# Channel.net
KiCad netlist of a schematic drawn in Altium Designer
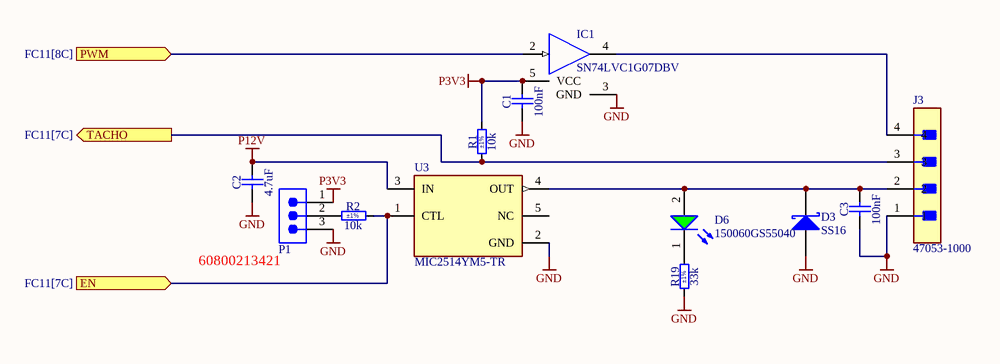
[diagram p0: Channel.SchDoc]

(export (version "E")
  (design (tool "Eeschema 10.0.6"))
  (components
    (comp (ref "C1")
      (value "100nF")
      (footprint "CAPC1005X55N")
      (description "Non-polarised capacitor")
      (fields
        (field (name "PART NUMBER") "CC0402_100NF_16V_10%_X5R")
        (field (name "VOLTAGE") "16V")
        (field (name "AUTHOR") "CERN DEM JLC")
      )
      (libsource (lib "Capacitors") (part "Capacitor - non polarized"))
    )
    (comp (ref "C2")
      (value "4.7uF")
      (footprint "CAPC1709X95N")
      (description "Non-polarised capacitor")
      (fields
        (field (name "PART NUMBER") "CC0603_4.7UF_16V_10%_X5R")
        (field (name "VOLTAGE") "16V")
        (field (name "AUTHOR") "CERN DEM JLC")
      )
      (libsource (lib "Capacitors") (part "Capacitor - non polarized"))
    )
    (comp (ref "C3")
      (value "100nF")
      (footprint "CAPC1005X55N")
      (description "Non-polarised capacitor")
      (fields
        (field (name "PART NUMBER") "CC0402_100NF_16V_10%_X5R")
        (field (name "VOLTAGE") "16V")
        (field (name "AUTHOR") "CERN DEM JLC")
      )
      (libsource (lib "Capacitors") (part "Capacitor - non polarized"))
    )
    (comp (ref "D3")
      (value "SS16")
      (footprint "FAIR-SMA-2_B_V")
      (description "Schottky Rectifier, 700 mV, -65 to 125 degC, 2-Pin SMA, RoHS, Tape and Reel")
      (fields (field (name "MANUFACTURER") "FairchildSemiconductor"))
      (libsource (lib "Altium Content Vault") (part "DSKY-AK-2"))
    )
    (comp (ref "D6")
      (value "150060GS55040")
      (footprint "WL-SMCD_0603")
      (description "150060GS55040 WL-SMCD SMT Mono-color Chip LED Diffused")
      (libsource (lib "Altium Content Vault") (part "LED_Green_2A-1K"))
    )
    (comp (ref "IC1")
      (value "SN74LVC1G07DBV")
      (footprint "SOT95P280X145-5N")
      (description "Single Buffer/Driver With Open-Drain Output")
      (fields (field (name "MANUFACTURER") "TEXAS INSTRUMENTS") (field (name "AUTHOR") "CERN DEM BC"))
      (libsource (lib "ICs And Semiconductors") (part "741G07"))
    )
    (comp (ref "J3")
      (value "47053-1000")
      (footprint "FP-470531000-MFG")
      (description "CONN HEADER VERT 4POS 2.54MM")
      (libsource (lib "Altium Content Vault") (part "299a8cea1bdcbc3624fe62c390fa72c"))
    )
    (comp (ref "P1")
      (value "~")
      (footprint "62000311121")
      (description "WR-PHD Pin Header, THT, Vertical, pitch 2mm, 1 Row, 3P")
      (fields
        (field (name "MANUFACTURER PART NUMBER") "62000311121")
        (field (name "MANUFACTURER") "Wurth Elektronik")
      )
      (libsource (lib "ALTIUM-WR-PHD_PIN_HEADER_SOCKET_HEADER-rev19a") (part "62000311121"))
    )
    (comp (ref "R1")
      (value "10k")
      (footprint "RESC1005X40N")
      (description "Resistor - 1%")
      (fields
        (field (name "TOLERANCE") "±1%")
        (field (name "PART NUMBER") "R0402_10K_1%_0.0625W_100PPM")
        (field (name "POWER") "0.0625W")
        (field (name "AUTHOR") "CERN DEM JLC")
      )
      (libsource (lib "Resistors") (part "Resistor - 1%"))
    )
    (comp (ref "R2")
      (value "10k")
      (footprint "RESC1005X40N")
      (description "Resistor - 1%")
      (fields
        (field (name "TOLERANCE") "±1%")
        (field (name "PART NUMBER") "R0402_10K_1%_0.0625W_100PPM")
        (field (name "POWER") "0.0625W")
        (field (name "AUTHOR") "CERN DEM JLC")
      )
      (libsource (lib "Resistors") (part "Resistor - 1%"))
    )
    (comp (ref "R19")
      (value "33k")
      (footprint "RESC1005X40N")
      (description "Resistor - 1%")
      (fields
        (field (name "TOLERANCE") "±1%")
        (field (name "PART NUMBER") "R0402_33K_1%_0.0625W_100PPM")
        (field (name "POWER") "0.0625W")
        (field (name "AUTHOR") "CERN DEM JLC")
      )
      (libsource (lib "Resistors") (part "Resistor - 1%"))
    )
    (comp (ref "U3")
      (value "MIC2514YM5-TR")
      (footprint "FP-SOT23-5LD-PL-1-IPC_A")
      (description "IC PWR SWITCH P-CHAN 1:1 SOT23-5")
      (libsource (lib "Altium Content Vault") (part "008eabdb66842fe748392592b2ae612"))
    )
  )
  (nets
    (net (code "1") (name "/EN") (class "Default")
      (node (ref "R2") (pin "2") (pinfunction "2_2") (pintype "passive"))
      (node (ref "U3") (pin "1") (pinfunction "CTL_1") (pintype "passive"))
    )
    (net (code "2") (name "/PWM") (class "Default")
      (node (ref "IC1") (pin "2") (pinfunction "IN_2") (pintype "input"))
    )
    (net (code "3") (name "/TACHO") (class "Default")
      (node (ref "J3") (pin "3") (pinfunction "3_3") (pintype "passive"))
      (node (ref "R1") (pin "1") (pinfunction "1_1") (pintype "passive"))
    )
    (net (code "4") (name "GND") (class "Default")
      (node (ref "C1") (pin "1") (pinfunction "1_1") (pintype "passive"))
      (node (ref "C2") (pin "1") (pinfunction "1_1") (pintype "passive"))
      (node (ref "C3") (pin "1") (pinfunction "1_1") (pintype "passive"))
      (node (ref "D3") (pin "1") (pinfunction "A_1") (pintype "passive"))
      (node (ref "IC1") (pin "3") (pinfunction "GND_3") (pintype "power_in"))
      (node (ref "J3") (pin "1") (pinfunction "1_1") (pintype "passive"))
      (node (ref "P1") (pin "3") (pinfunction "3_3") (pintype "passive"))
      (node (ref "R19") (pin "1") (pinfunction "1_1") (pintype "passive"))
      (node (ref "U3") (pin "2") (pinfunction "GND_2") (pintype "power_in"))
    )
    (net (code "5") (name "Net-(D3-K)") (class "Default")
      (node (ref "C3") (pin "2") (pinfunction "2_2") (pintype "passive"))
      (node (ref "D3") (pin "2") (pinfunction "K_2") (pintype "passive"))
      (node (ref "D6") (pin "2") (pinfunction "A_2") (pintype "passive"))
      (node (ref "J3") (pin "2") (pinfunction "2_2") (pintype "passive"))
      (node (ref "U3") (pin "4") (pinfunction "OUT_4") (pintype "output"))
    )
    (net (code "6") (name "Net-(D6-K)") (class "Default")
      (node (ref "D6") (pin "1") (pinfunction "K_1") (pintype "passive"))
      (node (ref "R19") (pin "2") (pinfunction "2_2") (pintype "passive"))
    )
    (net (code "7") (name "Net-(IC1-OUT)") (class "Default")
      (node (ref "IC1") (pin "4") (pinfunction "OUT_4") (pintype "open_collector"))
      (node (ref "J3") (pin "4") (pinfunction "4_4") (pintype "passive"))
    )
    (net (code "8") (name "Net-(P1-Pad2)") (class "Default")
      (node (ref "P1") (pin "2") (pinfunction "2_2") (pintype "passive"))
      (node (ref "R2") (pin "1") (pinfunction "1_1") (pintype "passive"))
    )
    (net (code "9") (name "P3V3") (class "Default")
      (node (ref "C1") (pin "2") (pinfunction "2_2") (pintype "passive"))
      (node (ref "IC1") (pin "5") (pinfunction "VCC_5") (pintype "power_in"))
      (node (ref "P1") (pin "1") (pinfunction "1_1") (pintype "passive"))
      (node (ref "R1") (pin "2") (pinfunction "2_2") (pintype "passive"))
    )
    (net (code "10") (name "P12V") (class "Default")
      (node (ref "C2") (pin "2") (pinfunction "2_2") (pintype "passive"))
      (node (ref "U3") (pin "3") (pinfunction "IN_3") (pintype "power_in"))
    )
    (net (code "11") (name "unconnected-(U3-NC-Pad5)") (class "Default")
      (node (ref "U3") (pin "5") (pinfunction "NC_5") (pintype "passive"))
    )
  )
)
